# Banks.net
KiCad netlist of a schematic drawn in Altium Designer
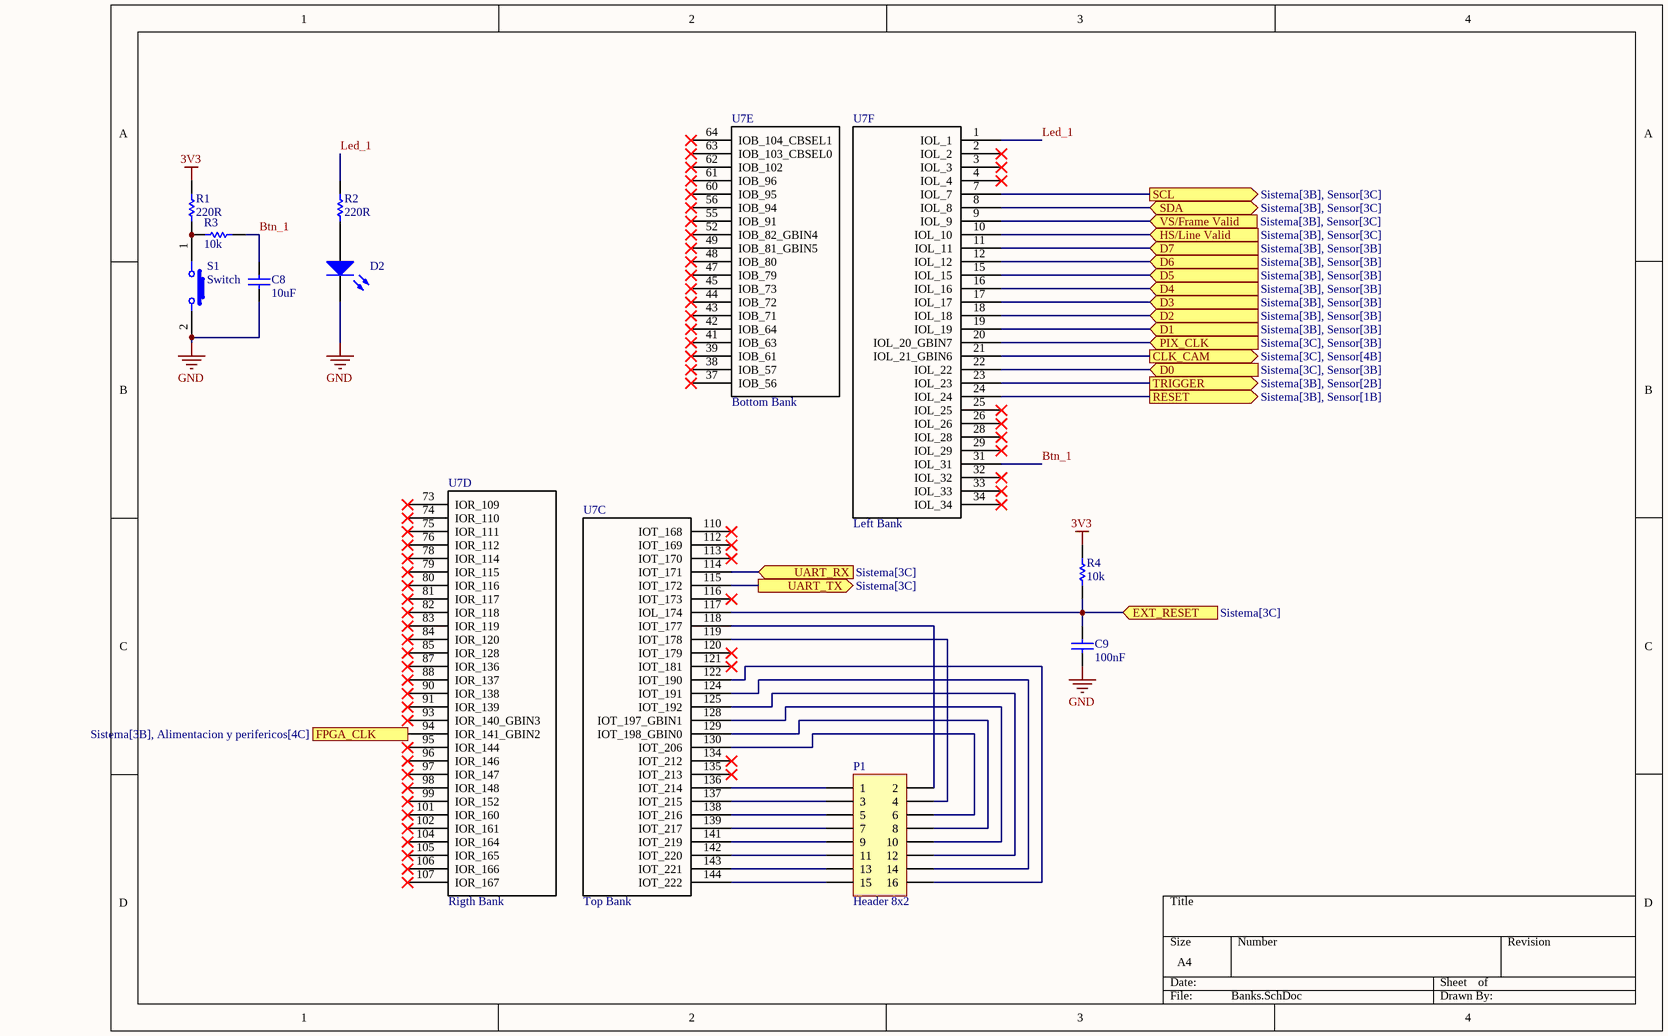
[diagram p0: Banks.SchDoc]

(export (version "E")
  (design (tool "Eeschema 10.0.6"))
  (components
    (comp (ref "C8")
      (value "10uF")
      (footprint "C_1206_3216_A")
      (description "Capacitor SMD 1206")
      (fields (field (name "TOLERANCE") "10%") (field (name "MANUFACTURER") "Samsung"))
      (libsource (lib "MyLibraryV2") (part "C_10uF_25V_c"))
    )
    (comp (ref "C9")
      (value "100nF")
      (footprint "C_0805_2013_b")
      (description "Capacitor SMD 0805")
      (fields (field (name "TOLERANCE") "10%") (field (name "VOLTAGE") "50V"))
      (libsource (lib "MyLibraryV2") (part "C_100nF_50V_b"))
    )
    (comp (ref "D2")
      (value "GREEN")
      (footprint "D_LED_0805_2013")
      (description "(Modificar) Diode SMD 0805")
      (libsource (lib "MyLibraryV2") (part "D_LED_SMD_0805"))
    )
    (comp (ref "P1")
      (value "Header 8x2")
      (footprint "P_HDR2X8_3D")
      (libsource (lib "MyLibraryV2") (part "P_Conector 8x2"))
    )
    (comp (ref "R1")
      (value "220R")
      (footprint "R_0805_2012_a")
      (description "Resistor SMD 0805")
      (fields (field (name "TOLERANCE") "1%") (field (name "MANUFACTURER") "Bourns"))
      (libsource (lib "MyLibraryV2") (part "R_220R_b"))
    )
    (comp (ref "R2")
      (value "220R")
      (footprint "R_0805_2012_a")
      (description "Resistor SMD 0805")
      (fields (field (name "TOLERANCE") "1%") (field (name "MANUFACTURER") "Bourns"))
      (libsource (lib "MyLibraryV2") (part "R_220R_b"))
    )
    (comp (ref "R3")
      (value "10k")
      (footprint "R_0805_2012_a")
      (description "Resistor SMD 0805")
      (fields (field (name "TOLERANCE") "1%") (field (name "MANUFACTURER") "Yageo"))
      (libsource (lib "MyLibraryV2") (part "R_10k_b"))
    )
    (comp (ref "R4")
      (value "10k")
      (footprint "R_0805_2012_a")
      (description "Resistor SMD 0805")
      (fields (field (name "TOLERANCE") "1%") (field (name "MANUFACTURER") "Yageo"))
      (libsource (lib "MyLibraryV2") (part "R_10k_b"))
    )
    (comp (ref "S1")
      (value "Switch")
      (footprint "S_SMD_SPST-NO")
      (description "(Generico) Switch SMD")
      (libsource (lib "MyLibraryV2") (part "S_?_3"))
    )
    (comp (ref "U7") (value "Top Bank") (footprint "U_TQFP-144") (libsource (lib "") (part "U_iCE40HX4K_1")))
  )
  (nets
    (net (code "1") (name "/Btn_1") (class "Default")
      (node (ref "C8") (pin "2") (pinfunction "2_2") (pintype "passive"))
      (node (ref "R3") (pin "2") (pinfunction "2_2") (pintype "passive"))
      (node (ref "U7") (pin "31") (pinfunction "IOL_31_31") (pintype "passive"))
    )
    (net (code "2") (name "/CLK_CAM") (class "Default")
      (node (ref "U7") (pin "21") (pinfunction "IOL_21_GBIN6_21") (pintype "passive"))
    )
    (net (code "3") (name "/D0") (class "Default")
      (node (ref "U7") (pin "22") (pinfunction "IOL_22_22") (pintype "passive"))
    )
    (net (code "4") (name "/D1") (class "Default")
      (node (ref "U7") (pin "19") (pinfunction "IOL_19_19") (pintype "passive"))
    )
    (net (code "5") (name "/D2") (class "Default")
      (node (ref "U7") (pin "18") (pinfunction "IOL_18_18") (pintype "passive"))
    )
    (net (code "6") (name "/D3") (class "Default")
      (node (ref "U7") (pin "17") (pinfunction "IOL_17_17") (pintype "passive"))
    )
    (net (code "7") (name "/D4") (class "Default")
      (node (ref "U7") (pin "16") (pinfunction "IOL_16_16") (pintype "passive"))
    )
    (net (code "8") (name "/D5") (class "Default")
      (node (ref "U7") (pin "15") (pinfunction "IOL_15_15") (pintype "passive"))
    )
    (net (code "9") (name "/D6") (class "Default")
      (node (ref "U7") (pin "12") (pinfunction "IOL_12_12") (pintype "passive"))
    )
    (net (code "10") (name "/D7") (class "Default")
      (node (ref "U7") (pin "11") (pinfunction "IOL_11_11") (pintype "passive"))
    )
    (net (code "11") (name "/EXT_RESET") (class "Default")
      (node (ref "C9") (pin "2") (pinfunction "2_2") (pintype "passive"))
      (node (ref "R4") (pin "1") (pinfunction "1_1") (pintype "passive"))
      (node (ref "U7") (pin "117") (pinfunction "IOL_174_117") (pintype "passive"))
    )
    (net (code "12") (name "/FPGA_CLK") (class "Default")
      (node (ref "U7") (pin "94") (pinfunction "IOR_141_GBIN2_94") (pintype "passive"))
    )
    (net (code "13") (name "/HS{slash}Line Valid") (class "Default")
      (node (ref "U7") (pin "10") (pinfunction "IOL_10_10") (pintype "passive"))
    )
    (net (code "14") (name "/Led_1") (class "Default")
      (node (ref "R2") (pin "2") (pinfunction "2_2") (pintype "passive"))
      (node (ref "U7") (pin "1") (pinfunction "IOL_1_1") (pintype "passive"))
    )
    (net (code "15") (name "/PIX_CLK") (class "Default")
      (node (ref "U7") (pin "20") (pinfunction "IOL_20_GBIN7_20") (pintype "passive"))
    )
    (net (code "16") (name "/RESET") (class "Default")
      (node (ref "U7") (pin "24") (pinfunction "IOL_24_24") (pintype "passive"))
    )
    (net (code "17") (name "/SCL") (class "Default")
      (node (ref "U7") (pin "7") (pinfunction "IOL_7_7") (pintype "passive"))
    )
    (net (code "18") (name "/SDA") (class "Default")
      (node (ref "U7") (pin "8") (pinfunction "IOL_8_8") (pintype "passive"))
    )
    (net (code "19") (name "/TRIGGER") (class "Default")
      (node (ref "U7") (pin "23") (pinfunction "IOL_23_23") (pintype "passive"))
    )
    (net (code "20") (name "/UART_RX") (class "Default")
      (node (ref "U7") (pin "114") (pinfunction "IOT_171_114") (pintype "passive"))
    )
    (net (code "21") (name "/UART_TX") (class "Default")
      (node (ref "U7") (pin "115") (pinfunction "IOT_172_115") (pintype "passive"))
    )
    (net (code "22") (name "/VS{slash}Frame Valid") (class "Default")
      (node (ref "U7") (pin "9") (pinfunction "IOL_9_9") (pintype "passive"))
    )
    (net (code "23") (name "3V3") (class "Default")
      (node (ref "R1") (pin "2") (pinfunction "2_2") (pintype "passive"))
      (node (ref "R4") (pin "2") (pinfunction "2_2") (pintype "passive"))
    )
    (net (code "24") (name "GND") (class "Default")
      (node (ref "C8") (pin "1") (pinfunction "1_1") (pintype "passive"))
      (node (ref "C9") (pin "1") (pinfunction "1_1") (pintype "passive"))
      (node (ref "D2") (pin "1") (pinfunction "K_1") (pintype "passive"))
      (node (ref "S1") (pin "2") (pinfunction "2_2") (pintype "passive"))
    )
    (net (code "25") (name "Net-(D2-A)") (class "Default")
      (node (ref "D2") (pin "2") (pinfunction "A_2") (pintype "passive"))
      (node (ref "R2") (pin "1") (pinfunction "1_1") (pintype "passive"))
    )
    (net (code "26") (name "Net-(R1-Pad1)") (class "Default")
      (node (ref "R1") (pin "1") (pinfunction "1_1") (pintype "passive"))
      (node (ref "R3") (pin "1") (pinfunction "1_1") (pintype "passive"))
      (node (ref "S1") (pin "1") (pinfunction "1_1") (pintype "passive"))
    )
    (net (code "27") (name "Net-(U7C-IOT_177)") (class "Default")
      (node (ref "P1") (pin "2") (pinfunction "2_2") (pintype "passive"))
      (node (ref "U7") (pin "118") (pinfunction "IOT_177_118") (pintype "passive"))
    )
    (net (code "28") (name "Net-(U7C-IOT_178)") (class "Default")
      (node (ref "P1") (pin "4") (pinfunction "4_4") (pintype "passive"))
      (node (ref "U7") (pin "119") (pinfunction "IOT_178_119") (pintype "passive"))
    )
    (net (code "29") (name "Net-(U7C-IOT_190)") (class "Default")
      (node (ref "P1") (pin "16") (pinfunction "16_16") (pintype "passive"))
      (node (ref "U7") (pin "122") (pinfunction "IOT_190_122") (pintype "passive"))
    )
    (net (code "30") (name "Net-(U7C-IOT_191)") (class "Default")
      (node (ref "P1") (pin "14") (pinfunction "14_14") (pintype "passive"))
      (node (ref "U7") (pin "124") (pinfunction "IOT_191_124") (pintype "passive"))
    )
    (net (code "31") (name "Net-(U7C-IOT_192)") (class "Default")
      (node (ref "P1") (pin "12") (pinfunction "12_12") (pintype "passive"))
      (node (ref "U7") (pin "125") (pinfunction "IOT_192_125") (pintype "passive"))
    )
    (net (code "32") (name "Net-(U7C-IOT_197_GBIN1)") (class "Default")
      (node (ref "P1") (pin "10") (pinfunction "10_10") (pintype "passive"))
      (node (ref "U7") (pin "128") (pinfunction "IOT_197_GBIN1_128") (pintype "passive"))
    )
    (net (code "33") (name "Net-(U7C-IOT_198_GBIN0)") (class "Default")
      (node (ref "P1") (pin "8") (pinfunction "8_8") (pintype "passive"))
      (node (ref "U7") (pin "129") (pinfunction "IOT_198_GBIN0_129") (pintype "passive"))
    )
    (net (code "34") (name "Net-(U7C-IOT_206)") (class "Default")
      (node (ref "P1") (pin "6") (pinfunction "6_6") (pintype "passive"))
      (node (ref "U7") (pin "130") (pinfunction "IOT_206_130") (pintype "passive"))
    )
    (net (code "35") (name "Net-(U7C-IOT_214)") (class "Default")
      (node (ref "P1") (pin "1") (pinfunction "1_1") (pintype "passive"))
      (node (ref "U7") (pin "136") (pinfunction "IOT_214_136") (pintype "passive"))
    )
    (net (code "36") (name "Net-(U7C-IOT_215)") (class "Default")
      (node (ref "P1") (pin "3") (pinfunction "3_3") (pintype "passive"))
      (node (ref "U7") (pin "137") (pinfunction "IOT_215_137") (pintype "passive"))
    )
    (net (code "37") (name "Net-(U7C-IOT_216)") (class "Default")
      (node (ref "P1") (pin "5") (pinfunction "5_5") (pintype "passive"))
      (node (ref "U7") (pin "138") (pinfunction "IOT_216_138") (pintype "passive"))
    )
    (net (code "38") (name "Net-(U7C-IOT_217)") (class "Default")
      (node (ref "P1") (pin "7") (pinfunction "7_7") (pintype "passive"))
      (node (ref "U7") (pin "139") (pinfunction "IOT_217_139") (pintype "passive"))
    )
    (net (code "39") (name "Net-(U7C-IOT_219)") (class "Default")
      (node (ref "P1") (pin "9") (pinfunction "9_9") (pintype "passive"))
      (node (ref "U7") (pin "141") (pinfunction "IOT_219_141") (pintype "passive"))
    )
    (net (code "40") (name "Net-(U7C-IOT_220)") (class "Default")
      (node (ref "P1") (pin "11") (pinfunction "11_11") (pintype "passive"))
      (node (ref "U7") (pin "142") (pinfunction "IOT_220_142") (pintype "passive"))
    )
    (net (code "41") (name "Net-(U7C-IOT_221)") (class "Default")
      (node (ref "P1") (pin "13") (pinfunction "13_13") (pintype "passive"))
      (node (ref "U7") (pin "143") (pinfunction "IOT_221_143") (pintype "passive"))
    )
    (net (code "42") (name "Net-(U7C-IOT_222)") (class "Default")
      (node (ref "P1") (pin "15") (pinfunction "15_15") (pintype "passive"))
      (node (ref "U7") (pin "144") (pinfunction "IOT_222_144") (pintype "passive"))
    )
    (net (code "43") (name "unconnected-(U7C-IOT_168-Pad110)") (class "Default")
      (node (ref "U7") (pin "110") (pinfunction "IOT_168_110") (pintype "passive+no_connect"))
    )
    (net (code "44") (name "unconnected-(U7C-IOT_169-Pad112)") (class "Default")
      (node (ref "U7") (pin "112") (pinfunction "IOT_169_112") (pintype "passive+no_connect"))
    )
    (net (code "45") (name "unconnected-(U7C-IOT_170-Pad113)") (class "Default")
      (node (ref "U7") (pin "113") (pinfunction "IOT_170_113") (pintype "passive+no_connect"))
    )
    (net (code "46") (name "unconnected-(U7C-IOT_173-Pad116)") (class "Default")
      (node (ref "U7") (pin "116") (pinfunction "IOT_173_116") (pintype "passive+no_connect"))
    )
    (net (code "47") (name "unconnected-(U7C-IOT_179-Pad120)") (class "Default")
      (node (ref "U7") (pin "120") (pinfunction "IOT_179_120") (pintype "passive+no_connect"))
    )
    (net (code "48") (name "unconnected-(U7C-IOT_181-Pad121)") (class "Default")
      (node (ref "U7") (pin "121") (pinfunction "IOT_181_121") (pintype "passive+no_connect"))
    )
    (net (code "49") (name "unconnected-(U7C-IOT_212-Pad134)") (class "Default")
      (node (ref "U7") (pin "134") (pinfunction "IOT_212_134") (pintype "passive+no_connect"))
    )
    (net (code "50") (name "unconnected-(U7C-IOT_213-Pad135)") (class "Default")
      (node (ref "U7") (pin "135") (pinfunction "IOT_213_135") (pintype "passive+no_connect"))
    )
    (net (code "51") (name "unconnected-(U7D-IOR_109-Pad73)") (class "Default")
      (node (ref "U7") (pin "73") (pinfunction "IOR_109_73") (pintype "passive+no_connect"))
    )
    (net (code "52") (name "unconnected-(U7D-IOR_110-Pad74)") (class "Default")
      (node (ref "U7") (pin "74") (pinfunction "IOR_110_74") (pintype "passive+no_connect"))
    )
    (net (code "53") (name "unconnected-(U7D-IOR_111-Pad75)") (class "Default")
      (node (ref "U7") (pin "75") (pinfunction "IOR_111_75") (pintype "passive+no_connect"))
    )
    (net (code "54") (name "unconnected-(U7D-IOR_112-Pad76)") (class "Default")
      (node (ref "U7") (pin "76") (pinfunction "IOR_112_76") (pintype "passive+no_connect"))
    )
    (net (code "55") (name "unconnected-(U7D-IOR_114-Pad78)") (class "Default")
      (node (ref "U7") (pin "78") (pinfunction "IOR_114_78") (pintype "passive+no_connect"))
    )
    (net (code "56") (name "unconnected-(U7D-IOR_115-Pad79)") (class "Default")
      (node (ref "U7") (pin "79") (pinfunction "IOR_115_79") (pintype "passive+no_connect"))
    )
    (net (code "57") (name "unconnected-(U7D-IOR_116-Pad80)") (class "Default")
      (node (ref "U7") (pin "80") (pinfunction "IOR_116_80") (pintype "passive+no_connect"))
    )
    (net (code "58") (name "unconnected-(U7D-IOR_117-Pad81)") (class "Default")
      (node (ref "U7") (pin "81") (pinfunction "IOR_117_81") (pintype "passive+no_connect"))
    )
    (net (code "59") (name "unconnected-(U7D-IOR_118-Pad82)") (class "Default")
      (node (ref "U7") (pin "82") (pinfunction "IOR_118_82") (pintype "passive+no_connect"))
    )
    (net (code "60") (name "unconnected-(U7D-IOR_119-Pad83)") (class "Default")
      (node (ref "U7") (pin "83") (pinfunction "IOR_119_83") (pintype "passive+no_connect"))
    )
    (net (code "61") (name "unconnected-(U7D-IOR_120-Pad84)") (class "Default")
      (node (ref "U7") (pin "84") (pinfunction "IOR_120_84") (pintype "passive+no_connect"))
    )
    (net (code "62") (name "unconnected-(U7D-IOR_128-Pad85)") (class "Default")
      (node (ref "U7") (pin "85") (pinfunction "IOR_128_85") (pintype "passive+no_connect"))
    )
    (net (code "63") (name "unconnected-(U7D-IOR_136-Pad87)") (class "Default")
      (node (ref "U7") (pin "87") (pinfunction "IOR_136_87") (pintype "passive+no_connect"))
    )
    (net (code "64") (name "unconnected-(U7D-IOR_137-Pad88)") (class "Default")
      (node (ref "U7") (pin "88") (pinfunction "IOR_137_88") (pintype "passive+no_connect"))
    )
    (net (code "65") (name "unconnected-(U7D-IOR_138-Pad90)") (class "Default")
      (node (ref "U7") (pin "90") (pinfunction "IOR_138_90") (pintype "passive+no_connect"))
    )
    (net (code "66") (name "unconnected-(U7D-IOR_139-Pad91)") (class "Default")
      (node (ref "U7") (pin "91") (pinfunction "IOR_139_91") (pintype "passive+no_connect"))
    )
    (net (code "67") (name "unconnected-(U7D-IOR_140_GBIN3-Pad93)") (class "Default")
      (node (ref "U7") (pin "93") (pinfunction "IOR_140_GBIN3_93") (pintype "passive+no_connect"))
    )
    (net (code "68") (name "unconnected-(U7D-IOR_144-Pad95)") (class "Default")
      (node (ref "U7") (pin "95") (pinfunction "IOR_144_95") (pintype "passive+no_connect"))
    )
    (net (code "69") (name "unconnected-(U7D-IOR_146-Pad96)") (class "Default")
      (node (ref "U7") (pin "96") (pinfunction "IOR_146_96") (pintype "passive+no_connect"))
    )
    (net (code "70") (name "unconnected-(U7D-IOR_147-Pad97)") (class "Default")
      (node (ref "U7") (pin "97") (pinfunction "IOR_147_97") (pintype "passive+no_connect"))
    )
    (net (code "71") (name "unconnected-(U7D-IOR_148-Pad98)") (class "Default")
      (node (ref "U7") (pin "98") (pinfunction "IOR_148_98") (pintype "passive+no_connect"))
    )
    (net (code "72") (name "unconnected-(U7D-IOR_152-Pad99)") (class "Default")
      (node (ref "U7") (pin "99") (pinfunction "IOR_152_99") (pintype "passive+no_connect"))
    )
    (net (code "73") (name "unconnected-(U7D-IOR_160-Pad101)") (class "Default")
      (node (ref "U7") (pin "101") (pinfunction "IOR_160_101") (pintype "passive+no_connect"))
    )
    (net (code "74") (name "unconnected-(U7D-IOR_161-Pad102)") (class "Default")
      (node (ref "U7") (pin "102") (pinfunction "IOR_161_102") (pintype "passive+no_connect"))
    )
    (net (code "75") (name "unconnected-(U7D-IOR_164-Pad104)") (class "Default")
      (node (ref "U7") (pin "104") (pinfunction "IOR_164_104") (pintype "passive+no_connect"))
    )
    (net (code "76") (name "unconnected-(U7D-IOR_165-Pad105)") (class "Default")
      (node (ref "U7") (pin "105") (pinfunction "IOR_165_105") (pintype "passive+no_connect"))
    )
    (net (code "77") (name "unconnected-(U7D-IOR_166-Pad106)") (class "Default")
      (node (ref "U7") (pin "106") (pinfunction "IOR_166_106") (pintype "passive+no_connect"))
    )
    (net (code "78") (name "unconnected-(U7D-IOR_167-Pad107)") (class "Default")
      (node (ref "U7") (pin "107") (pinfunction "IOR_167_107") (pintype "passive+no_connect"))
    )
    (net (code "79") (name "unconnected-(U7E-IOB_56-Pad37)") (class "Default")
      (node (ref "U7") (pin "37") (pinfunction "IOB_56_37") (pintype "passive+no_connect"))
    )
    (net (code "80") (name "unconnected-(U7E-IOB_57-Pad38)") (class "Default")
      (node (ref "U7") (pin "38") (pinfunction "IOB_57_38") (pintype "passive+no_connect"))
    )
    (net (code "81") (name "unconnected-(U7E-IOB_61-Pad39)") (class "Default")
      (node (ref "U7") (pin "39") (pinfunction "IOB_61_39") (pintype "passive+no_connect"))
    )
    (net (code "82") (name "unconnected-(U7E-IOB_63-Pad41)") (class "Default")
      (node (ref "U7") (pin "41") (pinfunction "IOB_63_41") (pintype "passive+no_connect"))
    )
    (net (code "83") (name "unconnected-(U7E-IOB_64-Pad42)") (class "Default")
      (node (ref "U7") (pin "42") (pinfunction "IOB_64_42") (pintype "passive+no_connect"))
    )
    (net (code "84") (name "unconnected-(U7E-IOB_71-Pad43)") (class "Default")
      (node (ref "U7") (pin "43") (pinfunction "IOB_71_43") (pintype "passive+no_connect"))
    )
    (net (code "85") (name "unconnected-(U7E-IOB_72-Pad44)") (class "Default")
      (node (ref "U7") (pin "44") (pinfunction "IOB_72_44") (pintype "passive+no_connect"))
    )
    (net (code "86") (name "unconnected-(U7E-IOB_73-Pad45)") (class "Default")
      (node (ref "U7") (pin "45") (pinfunction "IOB_73_45") (pintype "passive+no_connect"))
    )
    (net (code "87") (name "unconnected-(U7E-IOB_79-Pad47)") (class "Default")
      (node (ref "U7") (pin "47") (pinfunction "IOB_79_47") (pintype "passive+no_connect"))
    )
    (net (code "88") (name "unconnected-(U7E-IOB_80-Pad48)") (class "Default")
      (node (ref "U7") (pin "48") (pinfunction "IOB_80_48") (pintype "passive+no_connect"))
    )
    (net (code "89") (name "unconnected-(U7E-IOB_81_GBIN5-Pad49)") (class "Default")
      (node (ref "U7") (pin "49") (pinfunction "IOB_81_GBIN5_49") (pintype "passive+no_connect"))
    )
    (net (code "90") (name "unconnected-(U7E-IOB_82_GBIN4-Pad52)") (class "Default")
      (node (ref "U7") (pin "52") (pinfunction "IOB_82_GBIN4_52") (pintype "passive+no_connect"))
    )
    (net (code "91") (name "unconnected-(U7E-IOB_91-Pad55)") (class "Default")
      (node (ref "U7") (pin "55") (pinfunction "IOB_91_55") (pintype "passive+no_connect"))
    )
    (net (code "92") (name "unconnected-(U7E-IOB_94-Pad56)") (class "Default")
      (node (ref "U7") (pin "56") (pinfunction "IOB_94_56") (pintype "passive+no_connect"))
    )
    (net (code "93") (name "unconnected-(U7E-IOB_95-Pad60)") (class "Default")
      (node (ref "U7") (pin "60") (pinfunction "IOB_95_60") (pintype "passive+no_connect"))
    )
    (net (code "94") (name "unconnected-(U7E-IOB_96-Pad61)") (class "Default")
      (node (ref "U7") (pin "61") (pinfunction "IOB_96_61") (pintype "passive+no_connect"))
    )
    (net (code "95") (name "unconnected-(U7E-IOB_102-Pad62)") (class "Default")
      (node (ref "U7") (pin "62") (pinfunction "IOB_102_62") (pintype "passive+no_connect"))
    )
    (net (code "96") (name "unconnected-(U7E-IOB_103_CBSEL0-Pad63)") (class "Default")
      (node (ref "U7") (pin "63") (pinfunction "IOB_103_CBSEL0_63") (pintype "passive+no_connect"))
    )
    (net (code "97") (name "unconnected-(U7E-IOB_104_CBSEL1-Pad64)") (class "Default")
      (node (ref "U7") (pin "64") (pinfunction "IOB_104_CBSEL1_64") (pintype "passive+no_connect"))
    )
    (net (code "98") (name "unconnected-(U7F-IOL_2-Pad2)") (class "Default")
      (node (ref "U7") (pin "2") (pinfunction "IOL_2_2") (pintype "passive+no_connect"))
    )
    (net (code "99") (name "unconnected-(U7F-IOL_3-Pad3)") (class "Default")
      (node (ref "U7") (pin "3") (pinfunction "IOL_3_3") (pintype "passive+no_connect"))
    )
    (net (code "100") (name "unconnected-(U7F-IOL_4-Pad4)") (class "Default")
      (node (ref "U7") (pin "4") (pinfunction "IOL_4_4") (pintype "passive+no_connect"))
    )
    (net (code "101") (name "unconnected-(U7F-IOL_25-Pad25)") (class "Default")
      (node (ref "U7") (pin "25") (pinfunction "IOL_25_25") (pintype "passive+no_connect"))
    )
    (net (code "102") (name "unconnected-(U7F-IOL_26-Pad26)") (class "Default")
      (node (ref "U7") (pin "26") (pinfunction "IOL_26_26") (pintype "passive+no_connect"))
    )
    (net (code "103") (name "unconnected-(U7F-IOL_28-Pad28)") (class "Default")
      (node (ref "U7") (pin "28") (pinfunction "IOL_28_28") (pintype "passive+no_connect"))
    )
    (net (code "104") (name "unconnected-(U7F-IOL_29-Pad29)") (class "Default")
      (node (ref "U7") (pin "29") (pinfunction "IOL_29_29") (pintype "passive+no_connect"))
    )
    (net (code "105") (name "unconnected-(U7F-IOL_32-Pad32)") (class "Default")
      (node (ref "U7") (pin "32") (pinfunction "IOL_32_32") (pintype "passive+no_connect"))
    )
    (net (code "106") (name "unconnected-(U7F-IOL_33-Pad33)") (class "Default")
      (node (ref "U7") (pin "33") (pinfunction "IOL_33_33") (pintype "passive+no_connect"))
    )
    (net (code "107") (name "unconnected-(U7F-IOL_34-Pad34)") (class "Default")
      (node (ref "U7") (pin "34") (pinfunction "IOL_34_34") (pintype "passive+no_connect"))
    )
  )
)
